# SchemaSuperstar.net
KiCad netlist of a schematic drawn in Altium Designer
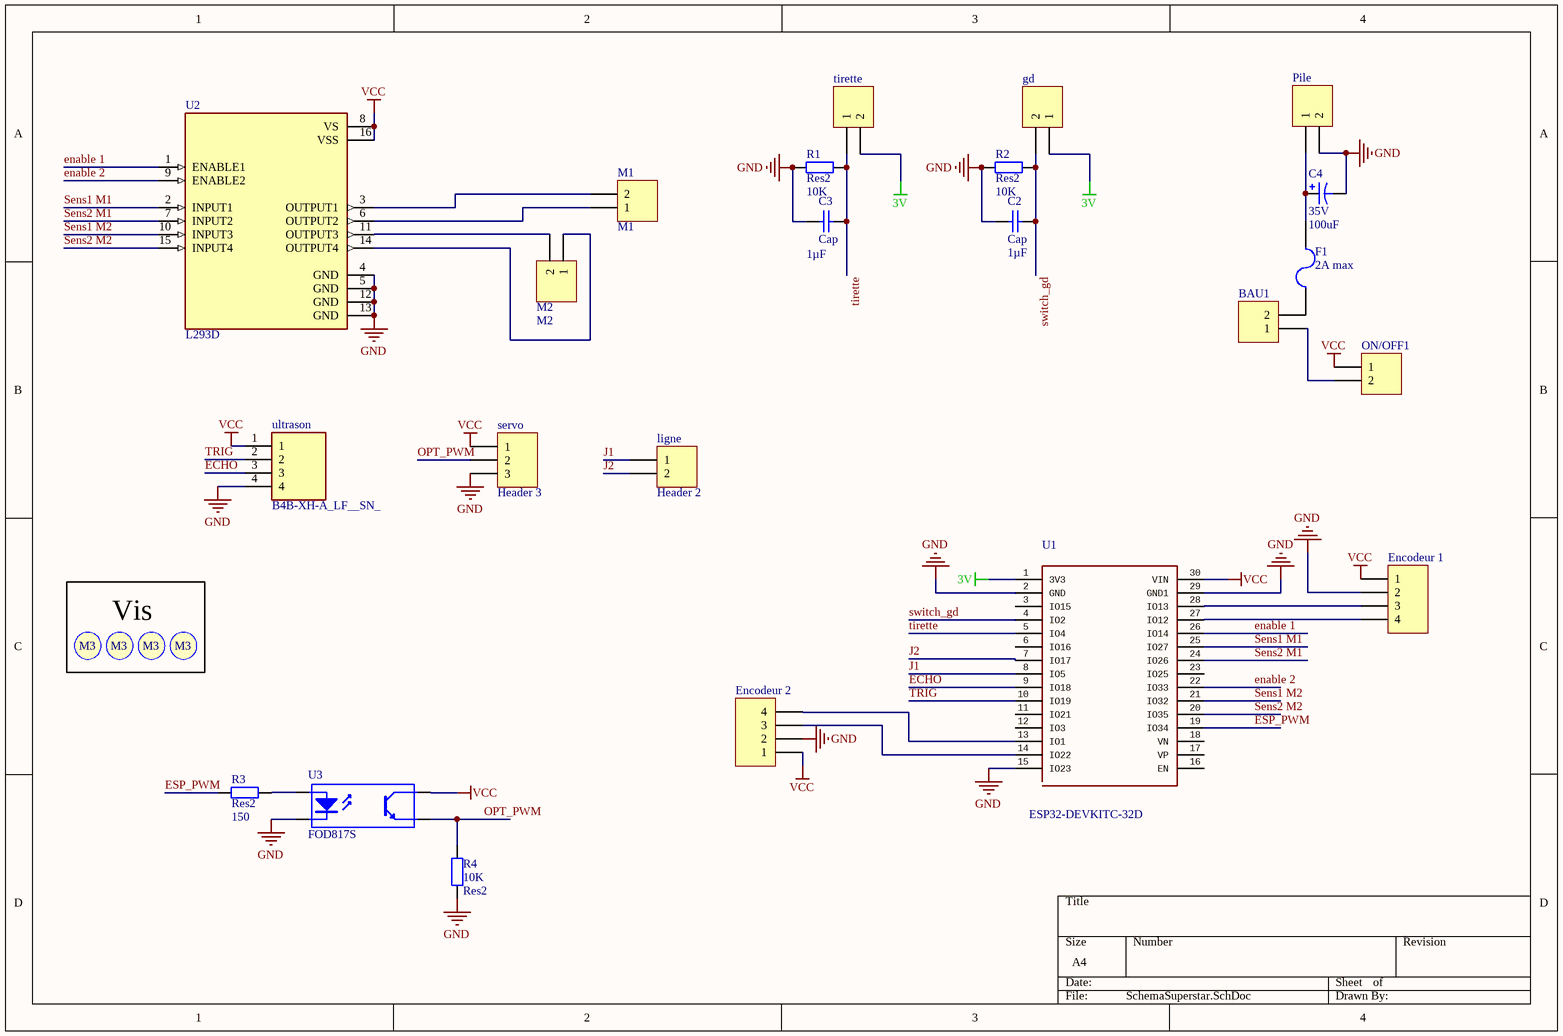
[diagram p0: SchemaSuperstar.SchDoc]

(export (version "E")
  (design (tool "Eeschema 10.0.6"))
  (components
    (comp (ref "BAU1")
      (value "~")
      (footprint "S2B-XH-A")
      (description "Header, 2-Pin, Right Angle")
      (fields (field (name "PUBLISHER") "Altium Limited"))
      (libsource (lib "Miscellaneous Connectors") (part "Header 2H"))
    )
    (comp (ref "C2")
      (value "Cap")
      (footprint "Capacitor 1206")
      (description "Capacitor")
      (fields (field (name "ALTIUM_VALUE") "1µF") (field (name "PUBLISHER") "Altium Limited"))
      (libsource (lib "Miscellaneous Devices") (part "Cap"))
    )
    (comp (ref "C3")
      (value "Cap")
      (footprint "Capacitor 1206")
      (description "Capacitor")
      (fields (field (name "ALTIUM_VALUE") "1µF") (field (name "PUBLISHER") "Altium Limited"))
      (libsource (lib "Miscellaneous Devices") (part "Cap"))
    )
    (comp (ref "C4")
      (value "35V")
      (footprint "Condensateur")
      (description "Polarized Capacitor (Radial)")
      (fields (field (name "ALTIUM_VALUE") "100uF") (field (name "PUBLISHER") "Altium Limited"))
      (libsource (lib "Miscellaneous Devices") (part "Cap Pol1"))
    )
    (comp (ref "Encodeur 1")
      (value "~")
      (footprint "B4BXHALFSN")
      (description "Header, 4-Pin, Right Angle")
      (fields (field (name "PUBLISHER") "Altium Limited"))
      (libsource (lib "Miscellaneous Connectors") (part "Header 4H"))
    )
    (comp (ref "Encodeur 2")
      (value "~")
      (footprint "B4BXHALFSN")
      (description "Header, 4-Pin, Right Angle")
      (fields (field (name "PUBLISHER") "Altium Limited"))
      (libsource (lib "") (part "Header 4H_1"))
    )
    (comp (ref "F1")
      (value "2A max")
      (footprint "PIN-W2/E2.8")
      (description "Fuse")
      (fields (field (name "PUBLISHER") "Altium Limited"))
      (libsource (lib "Miscellaneous Devices") (part "Fuse 2"))
    )
    (comp (ref "gd")
      (value "~")
      (footprint "S2B-XH-A")
      (description "Header, 2-Pin, Right Angle")
      (fields (field (name "PUBLISHER") "Altium Limited"))
      (libsource (lib "") (part "Header 2H_2"))
    )
    (comp (ref "ligne")
      (value "Header 2")
      (footprint "HDR1X2")
      (description "Header, 2-Pin")
      (fields (field (name "PUBLISHER") "Altium Limited"))
      (libsource (lib "Miscellaneous Connectors") (part "Header 2"))
    )
    (comp (ref "M1")
      (value "M1")
      (footprint "S2B-XH-A")
      (description "Header, 2-Pin, Right Angle")
      (fields (field (name "PUBLISHER") "Altium Limited"))
      (libsource (lib "") (part "Header 2H_1"))
    )
    (comp (ref "M2")
      (value "M2")
      (footprint "S2B-XH-A")
      (description "Header, 2-Pin, Right Angle")
      (fields (field (name "PUBLISHER") "Altium Limited"))
      (libsource (lib "") (part "Header 2H_3"))
    )
    (comp (ref "ON/OFF1")
      (value "~")
      (footprint "S2B-XH-A")
      (description "Header, 2-Pin, Right Angle")
      (fields (field (name "PUBLISHER") "Altium Limited"))
      (libsource (lib "") (part "Header 2H_2"))
    )
    (comp (ref "Pile")
      (value "~")
      (footprint "S2B-XH-A")
      (description "Header, 2-Pin, Right Angle")
      (fields (field (name "PUBLISHER") "Altium Limited"))
      (libsource (lib "") (part "Header 2H_1"))
    )
    (comp (ref "R1")
      (value "Res2")
      (footprint "Resistor 1206")
      (description "Resistor")
      (fields (field (name "ALTIUM_VALUE") "10K") (field (name "PUBLISHER") "Altium Limited"))
      (libsource (lib "Miscellaneous Devices") (part "Res2"))
    )
    (comp (ref "R2")
      (value "Res2")
      (footprint "Resistor 1206")
      (description "Resistor")
      (fields (field (name "ALTIUM_VALUE") "10K") (field (name "PUBLISHER") "Altium Limited"))
      (libsource (lib "Miscellaneous Devices") (part "Res2"))
    )
    (comp (ref "R3")
      (value "Res2")
      (footprint "Resistor 1206")
      (description "Resistor")
      (fields (field (name "ALTIUM_VALUE") "150") (field (name "PUBLISHER") "Altium Limited"))
      (libsource (lib "Miscellaneous Devices") (part "Res2"))
    )
    (comp (ref "R4")
      (value "Res2")
      (footprint "Resistor 1206")
      (description "Resistor")
      (fields (field (name "ALTIUM_VALUE") "10K") (field (name "PUBLISHER") "Altium Limited"))
      (libsource (lib "") (part "Res2_1"))
    )
    (comp (ref "S1")
      (value "Screw M3")
      (footprint "Screw M3")
      (libsource (lib "Robot_2019") (part "Screw M3"))
    )
    (comp (ref "S2")
      (value "Screw M3")
      (footprint "Screw M3")
      (libsource (lib "Robot_2019") (part "Screw M3"))
    )
    (comp (ref "S3")
      (value "Screw M3")
      (footprint "Screw M3")
      (libsource (lib "Robot_2019") (part "Screw M3"))
    )
    (comp (ref "S4")
      (value "Screw M3")
      (footprint "Screw M3")
      (libsource (lib "Robot_2019") (part "Screw M3"))
    )
    (comp (ref "servo")
      (value "Header 3")
      (footprint "HDR1X3")
      (description "Header, 3-Pin")
      (fields (field (name "PUBLISHER") "Altium Limited"))
      (libsource (lib "Miscellaneous Connectors") (part "Header 3"))
    )
    (comp (ref "tirette")
      (value "~")
      (footprint "S2B-XH-A")
      (description "Header, 2-Pin, Right Angle")
      (fields (field (name "PUBLISHER") "Altium Limited"))
      (libsource (lib "") (part "Header 2H_1"))
    )
    (comp (ref "U1")
      (value "ESP32-DEVKITC-32D")
      (footprint "MODULE_ESP32-DEVKITV1")
      (description "Eval Board For Esp-Wroom-32")
      (fields (field (name "MF") "Espressif Systems"))
      (libsource (lib "AltiumLibraryDDT") (part "ESP32-DEVKITC-32D"))
    )
    (comp (ref "U2")
      (value "L293D")
      (footprint "DIP880W50P254L2000H510Q16")
      (description "Bipolar Motor Driver - Parallel 16-PowerDIP")
      (fields (field (name "MF") "STMicroelectronics"))
      (libsource (lib "L293D") (part "L293D"))
    )
    (comp (ref "U3")
      (value "FOD817S")
      (footprint "SOP254P1016X385-4N")
      (description "4-Pin Phototransistor Optocoupler")
      (fields (field (name "PUBLISHER") "Altium Limited"))
      (libsource (lib "Miscellaneous Devices") (part "Optoisolator1"))
    )
    (comp (ref "ultrason")
      (value "B4B-XH-A_LF__SN_")
      (footprint "B4BXHALFSN")
      (description "Connector")
      (fields (field (name "MANUFACTURER_PART_NUMBER") "B4B-XH-A(LF)(SN)"))
      (libsource (lib "SamacSys") (part "B4B-XH-A_LF__SN_"))
    )
  )
  (nets
    (net (code "1") (name "/ECHO") (class "Default")
      (node (ref "U1") (pin "9") (pinfunction "IO18_9") (pintype "passive"))
      (node (ref "ultrason") (pin "3") (pinfunction "3_3") (pintype "passive"))
    )
    (net (code "2") (name "/ESP_PWM") (class "Default")
      (node (ref "R3") (pin "1") (pinfunction "1_1") (pintype "passive"))
      (node (ref "U1") (pin "19") (pinfunction "IO34_19") (pintype "passive"))
    )
    (net (code "3") (name "/J1") (class "Default")
      (node (ref "U1") (pin "8") (pinfunction "IO5_8") (pintype "passive"))
      (node (ref "ligne") (pin "1") (pinfunction "1_1") (pintype "passive"))
    )
    (net (code "4") (name "/J2") (class "Default")
      (node (ref "U1") (pin "7") (pinfunction "IO17_7") (pintype "passive"))
      (node (ref "ligne") (pin "2") (pinfunction "2_2") (pintype "passive"))
    )
    (net (code "5") (name "/OPT_PWM") (class "Default")
      (node (ref "R4") (pin "2") (pinfunction "2_2") (pintype "passive"))
      (node (ref "U3") (pin "3") (pinfunction "E_3") (pintype "passive"))
      (node (ref "servo") (pin "2") (pinfunction "2_2") (pintype "passive"))
    )
    (net (code "6") (name "/Sens1 M1") (class "Default")
      (node (ref "U1") (pin "25") (pinfunction "IO27_25") (pintype "passive"))
      (node (ref "U2") (pin "2") (pinfunction "INPUT1_2") (pintype "input"))
    )
    (net (code "7") (name "/Sens1 M2") (class "Default")
      (node (ref "U1") (pin "21") (pinfunction "IO32_21") (pintype "passive"))
      (node (ref "U2") (pin "10") (pinfunction "INPUT3_10") (pintype "input"))
    )
    (net (code "8") (name "/Sens2 M1") (class "Default")
      (node (ref "U1") (pin "24") (pinfunction "IO26_24") (pintype "passive"))
      (node (ref "U2") (pin "7") (pinfunction "INPUT2_7") (pintype "input"))
    )
    (net (code "9") (name "/Sens2 M2") (class "Default")
      (node (ref "U1") (pin "20") (pinfunction "IO35_20") (pintype "passive"))
      (node (ref "U2") (pin "15") (pinfunction "INPUT4_15") (pintype "input"))
    )
    (net (code "10") (name "/TRIG") (class "Default")
      (node (ref "U1") (pin "10") (pinfunction "IO19_10") (pintype "passive"))
      (node (ref "ultrason") (pin "2") (pinfunction "2_2") (pintype "passive"))
    )
    (net (code "11") (name "/enable 1") (class "Default")
      (node (ref "U1") (pin "26") (pinfunction "IO14_26") (pintype "passive"))
      (node (ref "U2") (pin "1") (pinfunction "ENABLE1_1") (pintype "input"))
    )
    (net (code "12") (name "/enable 2") (class "Default")
      (node (ref "U1") (pin "22") (pinfunction "IO33_22") (pintype "passive"))
      (node (ref "U2") (pin "9") (pinfunction "ENABLE2_9") (pintype "input"))
    )
    (net (code "13") (name "/switch_gd") (class "Default")
      (node (ref "C2") (pin "2") (pinfunction "2_2") (pintype "passive"))
      (node (ref "R2") (pin "2") (pinfunction "2_2") (pintype "passive"))
      (node (ref "U1") (pin "4") (pinfunction "IO2_4") (pintype "passive"))
      (node (ref "gd") (pin "2") (pinfunction "2_2") (pintype "passive"))
    )
    (net (code "14") (name "/tirette") (class "Default")
      (node (ref "C3") (pin "2") (pinfunction "2_2") (pintype "passive"))
      (node (ref "R1") (pin "2") (pinfunction "2_2") (pintype "passive"))
      (node (ref "U1") (pin "5") (pinfunction "IO4_5") (pintype "passive"))
      (node (ref "tirette") (pin "1") (pinfunction "1_1") (pintype "passive"))
    )
    (net (code "15") (name "3V") (class "Default")
      (node (ref "U1") (pin "1") (pinfunction "3V3_1") (pintype "passive"))
      (node (ref "gd") (pin "1") (pinfunction "1_1") (pintype "passive"))
      (node (ref "tirette") (pin "2") (pinfunction "2_2") (pintype "passive"))
    )
    (net (code "16") (name "GND") (class "Default")
      (node (ref "C2") (pin "1") (pinfunction "1_1") (pintype "passive"))
      (node (ref "C3") (pin "1") (pinfunction "1_1") (pintype "passive"))
      (node (ref "C4") (pin "2") (pinfunction "2_2") (pintype "passive"))
      (node (ref "Encodeur 1") (pin "2") (pinfunction "2_2") (pintype "passive"))
      (node (ref "Encodeur 2") (pin "2") (pinfunction "2_2") (pintype "passive"))
      (node (ref "Pile") (pin "2") (pinfunction "2_2") (pintype "passive"))
      (node (ref "R1") (pin "1") (pinfunction "1_1") (pintype "passive"))
      (node (ref "R2") (pin "1") (pinfunction "1_1") (pintype "passive"))
      (node (ref "R4") (pin "1") (pinfunction "1_1") (pintype "passive"))
      (node (ref "U1") (pin "15") (pinfunction "IO23_15") (pintype "passive"))
      (node (ref "U1") (pin "2") (pinfunction "GND_2") (pintype "passive"))
      (node (ref "U1") (pin "29") (pinfunction "GND1_29") (pintype "passive"))
      (node (ref "U2") (pin "12") (pinfunction "GND_12") (pintype "power_in"))
      (node (ref "U2") (pin "13") (pinfunction "GND_13") (pintype "power_in"))
      (node (ref "U2") (pin "4") (pinfunction "GND_4") (pintype "power_in"))
      (node (ref "U2") (pin "5") (pinfunction "GND_5") (pintype "power_in"))
      (node (ref "U3") (pin "2") (pinfunction "K_2") (pintype "passive"))
      (node (ref "servo") (pin "3") (pinfunction "3_3") (pintype "passive"))
      (node (ref "ultrason") (pin "4") (pinfunction "4_4") (pintype "passive"))
    )
    (net (code "17") (name "Net-(BAU1-Pad1)") (class "Default")
      (node (ref "BAU1") (pin "1") (pinfunction "1_1") (pintype "passive"))
      (node (ref "ON/OFF1") (pin "2") (pinfunction "2_2") (pintype "passive"))
    )
    (net (code "18") (name "Net-(BAU1-Pad2)") (class "Default")
      (node (ref "BAU1") (pin "2") (pinfunction "2_2") (pintype "passive"))
      (node (ref "F1") (pin "1") (pinfunction "1_1") (pintype "passive"))
    )
    (net (code "19") (name "Net-(C4-Pad1)") (class "Default")
      (node (ref "C4") (pin "1") (pinfunction "1_1") (pintype "passive"))
      (node (ref "F1") (pin "2") (pinfunction "2_2") (pintype "passive"))
      (node (ref "Pile") (pin "1") (pinfunction "1_1") (pintype "passive"))
    )
    (net (code "20") (name "Net-(U1-IO1)") (class "Default")
      (node (ref "Encodeur 2") (pin "4") (pinfunction "4_4") (pintype "passive"))
      (node (ref "U1") (pin "13") (pinfunction "IO1_13") (pintype "passive"))
    )
    (net (code "21") (name "Net-(U1-IO12)") (class "Default")
      (node (ref "Encodeur 1") (pin "4") (pinfunction "4_4") (pintype "passive"))
      (node (ref "U1") (pin "27") (pinfunction "IO12_27") (pintype "passive"))
    )
    (net (code "22") (name "Net-(U1-IO13)") (class "Default")
      (node (ref "Encodeur 1") (pin "3") (pinfunction "3_3") (pintype "passive"))
      (node (ref "U1") (pin "28") (pinfunction "IO13_28") (pintype "passive"))
    )
    (net (code "23") (name "Net-(U1-IO22)") (class "Default")
      (node (ref "Encodeur 2") (pin "3") (pinfunction "3_3") (pintype "passive"))
      (node (ref "U1") (pin "14") (pinfunction "IO22_14") (pintype "passive"))
    )
    (net (code "24") (name "Net-(U2-OUTPUT1)") (class "Default")
      (node (ref "M1") (pin "2") (pinfunction "2_2") (pintype "passive"))
      (node (ref "U2") (pin "3") (pinfunction "OUTPUT1_3") (pintype "output"))
    )
    (net (code "25") (name "Net-(U2-OUTPUT2)") (class "Default")
      (node (ref "M1") (pin "1") (pinfunction "1_1") (pintype "passive"))
      (node (ref "U2") (pin "6") (pinfunction "OUTPUT2_6") (pintype "output"))
    )
    (net (code "26") (name "Net-(U2-OUTPUT3)") (class "Default")
      (node (ref "M2") (pin "2") (pinfunction "2_2") (pintype "passive"))
      (node (ref "U2") (pin "11") (pinfunction "OUTPUT3_11") (pintype "output"))
    )
    (net (code "27") (name "Net-(U2-OUTPUT4)") (class "Default")
      (node (ref "M2") (pin "1") (pinfunction "1_1") (pintype "passive"))
      (node (ref "U2") (pin "14") (pinfunction "OUTPUT4_14") (pintype "output"))
    )
    (net (code "28") (name "Net-(U3-A)") (class "Default")
      (node (ref "R3") (pin "2") (pinfunction "2_2") (pintype "passive"))
      (node (ref "U3") (pin "1") (pinfunction "A_1") (pintype "passive"))
    )
    (net (code "29") (name "VCC") (class "Default")
      (node (ref "Encodeur 1") (pin "1") (pinfunction "1_1") (pintype "passive"))
      (node (ref "Encodeur 2") (pin "1") (pinfunction "1_1") (pintype "passive"))
      (node (ref "ON/OFF1") (pin "1") (pinfunction "1_1") (pintype "passive"))
      (node (ref "U1") (pin "30") (pinfunction "VIN_30") (pintype "passive"))
      (node (ref "U2") (pin "16") (pinfunction "VSS_16") (pintype "power_in"))
      (node (ref "U2") (pin "8") (pinfunction "VS_8") (pintype "power_in"))
      (node (ref "U3") (pin "4") (pinfunction "C_4") (pintype "passive"))
      (node (ref "servo") (pin "1") (pinfunction "1_1") (pintype "passive"))
      (node (ref "ultrason") (pin "1") (pinfunction "1_1") (pintype "passive"))
    )
    (net (code "30") (name "unconnected-(U1-EN-Pad16)") (class "Default")
      (node (ref "U1") (pin "16") (pinfunction "EN_16") (pintype "passive"))
    )
    (net (code "31") (name "unconnected-(U1-IO3-Pad12)") (class "Default")
      (node (ref "U1") (pin "12") (pinfunction "IO3_12") (pintype "passive"))
    )
    (net (code "32") (name "unconnected-(U1-IO15-Pad3)") (class "Default")
      (node (ref "U1") (pin "3") (pinfunction "IO15_3") (pintype "passive"))
    )
    (net (code "33") (name "unconnected-(U1-IO16-Pad6)") (class "Default")
      (node (ref "U1") (pin "6") (pinfunction "IO16_6") (pintype "passive"))
    )
    (net (code "34") (name "unconnected-(U1-IO21-Pad11)") (class "Default")
      (node (ref "U1") (pin "11") (pinfunction "IO21_11") (pintype "passive"))
    )
    (net (code "35") (name "unconnected-(U1-IO25-Pad23)") (class "Default")
      (node (ref "U1") (pin "23") (pinfunction "IO25_23") (pintype "passive"))
    )
    (net (code "36") (name "unconnected-(U1-VN-Pad18)") (class "Default")
      (node (ref "U1") (pin "18") (pinfunction "VN_18") (pintype "passive"))
    )
    (net (code "37") (name "unconnected-(U1-VP-Pad17)") (class "Default")
      (node (ref "U1") (pin "17") (pinfunction "VP_17") (pintype "passive"))
    )
  )
)
